# Adafruit_VEML7700_STEMMA_QT.net
KiCad netlist of a schematic drawn in Altium Designer
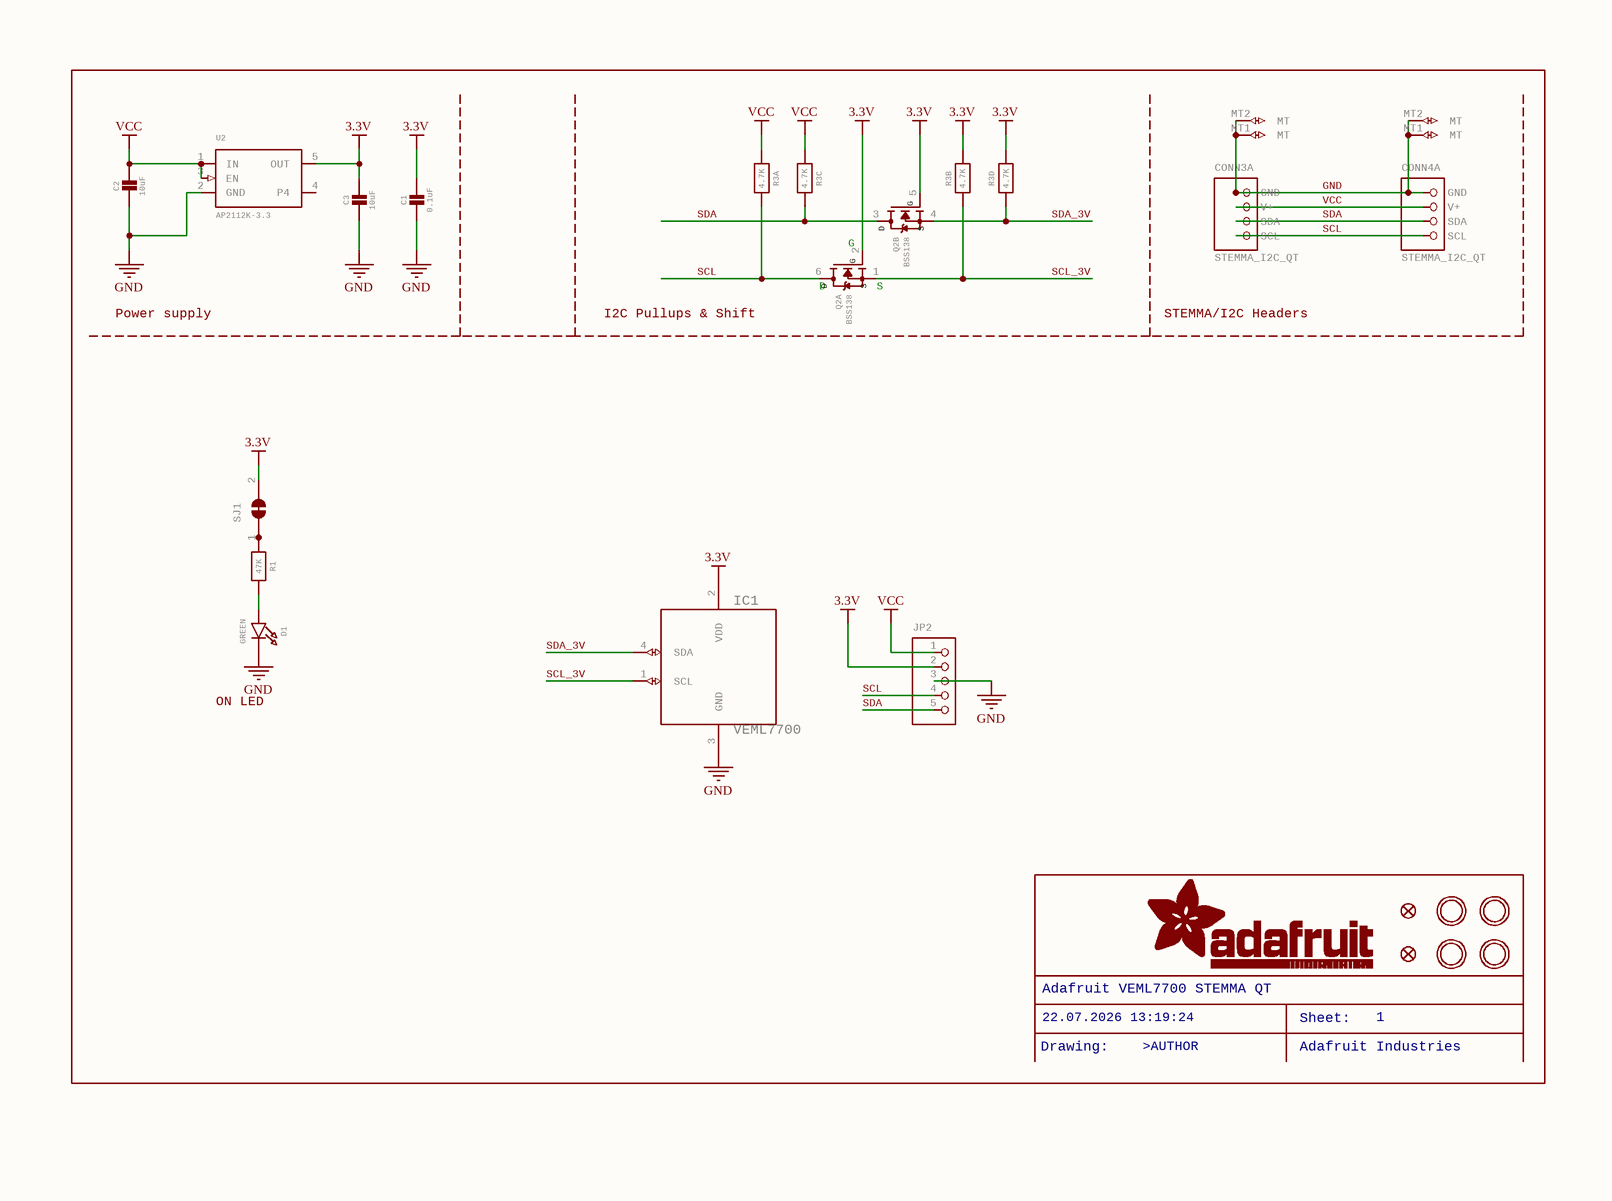
[diagram p0: Adafruit VEML7700 STEMMA QT.SchDoc]

(export (version "E")
  (design (tool "Eeschema 10.0.6"))
  (components
    (comp (ref "C1")
      (value "0.1uF")
      (footprint "0603-NO")
      (libsource (lib "microbuilder") (part "CAP_CERAMIC0603_NO"))
    )
    (comp (ref "C2")
      (value "10uF")
      (footprint "0805-NO")
      (libsource (lib "microbuilder") (part "CAP_CERAMIC0805-NOOUTLINE"))
    )
    (comp (ref "C3")
      (value "10uF")
      (footprint "0805-NO")
      (libsource (lib "microbuilder") (part "CAP_CERAMIC0805-NOOUTLINE"))
    )
    (comp (ref "CONN3")
      (value "STEMMA_I2C_QT")
      (footprint "JST_SH4")
      (libsource (lib "microbuilder") (part "STEMMA_I2C_QT"))
    )
    (comp (ref "CONN4")
      (value "STEMMA_I2C_QT")
      (footprint "JST_SH4")
      (libsource (lib "microbuilder") (part "STEMMA_I2C_QT"))
    )
    (comp (ref "D1")
      (value "GREEN")
      (footprint "CHIPLED_0603_NOOUTLINE")
      (libsource (lib "microbuilder") (part "LED0603_NOOUTLINE"))
    )
    (comp (ref "FID3")
      (value "FIDUCIAL_1MM")
      (footprint "FIDUCIAL_1MM")
      (description "Fiducial Alignment Points   Various fiducial points for machine vision alignment.")
      (libsource (lib "microbuilder") (part "FIDUCIAL_1MM"))
    )
    (comp (ref "FID4")
      (value "FIDUCIAL_1MM")
      (footprint "FIDUCIAL_1MM")
      (description "Fiducial Alignment Points   Various fiducial points for machine vision alignment.")
      (libsource (lib "microbuilder") (part "FIDUCIAL_1MM"))
    )
    (comp (ref "IC1")
      (value "VEML7700")
      (footprint "VEML7700")
      (fields (field (name "VEML7700") "VEML7700"))
      (libsource (lib "VEML7700") (part "VEML7700"))
    )
    (comp (ref "JP2")
      (value "HEADER-1X5ROUND")
      (footprint "1X05_ROUND")
      (description "PIN HEADER")
      (libsource (lib "microbuilder") (part "HEADER-1X5ROUND"))
    )
    (comp (ref "Q2")
      (value "BSS138")
      (footprint "SOT363")
      (description "Dual N-Channel MOSFET   SOT363 (2.0x1.25mm) 2N7002PS - 60V, 320mA [Digikey: 568-5984-1-ND]")
      (fields (field (name "D") "D") (field (name "S") "S") (field (name "G") "G"))
      (libsource (lib "microbuilder") (part "MOSFET-N_DUAL"))
    )
    (comp (ref "R1")
      (value "47K")
      (footprint "0603-NO")
      (libsource (lib "microbuilder") (part "RESISTOR_0603_NOOUT"))
    )
    (comp (ref "R3")
      (value "4.7K")
      (footprint "RESPACK_4X0603")
      (description "Resistor Packs (4 resistors)   4 x 0603 10K 1/16W - Digikey: YC164J-10KCT-ND")
      (libsource (lib "microbuilder") (part "RESISTOR_4PACK"))
    )
    (comp (ref "SJ1")
      (value "SOLDERJUMPER_CLOSED")
      (footprint "SOLDERJUMPER_CLOSEDWIRE")
      (libsource (lib "microbuilder") (part "SOLDERJUMPER_CLOSED"))
    )
    (comp (ref "U$1")
      (value "MOUNTINGHOLE2.5")
      (footprint "MOUNTINGHOLE_2.5_PLATED")
      (description "Mounting Hole   For #2 screws (0.086\"/2.18mm width, 0.094\"/2.4mm hole) use 2.5mm")
      (fields (field (name "LIBRARYNAME") "adafruit_electromech"))
      (libsource (lib "adafruit_electromech") (part "MOUNTINGHOLE2.5"))
    )
    (comp (ref "U$17")
      (value "MOUNTINGHOLE2.5")
      (footprint "MOUNTINGHOLE_2.5_PLATED")
      (description "Mounting Hole   For #2 screws (0.086\"/2.18mm width, 0.094\"/2.4mm hole) use 2.5mm")
      (fields (field (name "LIBRARYNAME") "adafruit_electromech"))
      (libsource (lib "adafruit_electromech") (part "MOUNTINGHOLE2.5"))
    )
    (comp (ref "U$19")
      (value "MOUNTINGHOLE2.5")
      (footprint "MOUNTINGHOLE_2.5_PLATED")
      (description "Mounting Hole   For #2 screws (0.086\"/2.18mm width, 0.094\"/2.4mm hole) use 2.5mm")
      (fields (field (name "LIBRARYNAME") "adafruit_electromech"))
      (libsource (lib "adafruit_electromech") (part "MOUNTINGHOLE2.5"))
    )
    (comp (ref "U$21")
      (value "MOUNTINGHOLE2.5")
      (footprint "MOUNTINGHOLE_2.5_PLATED")
      (description "Mounting Hole   For #2 screws (0.086\"/2.18mm width, 0.094\"/2.4mm hole) use 2.5mm")
      (fields (field (name "LIBRARYNAME") "adafruit_electromech"))
      (libsource (lib "adafruit_electromech") (part "MOUNTINGHOLE2.5"))
    )
    (comp (ref "U2")
      (value "AP2112K-3.3")
      (footprint "SOT23-5")
      (libsource (lib "adafruit_power") (part "VREG_SOT23-5"))
    )
  )
  (nets
    (net (code "1") (name "/SCL") (class "Default")
      (node (ref "CONN3") (pin "4") (pinfunction "SCL_4") (pintype "passive"))
      (node (ref "CONN4") (pin "4") (pinfunction "SCL_4") (pintype "passive"))
      (node (ref "JP2") (pin "4") (pinfunction "4_4") (pintype "passive"))
      (node (ref "Q2") (pin "6") (pinfunction "D_6") (pintype "bidirectional"))
      (node (ref "R3") (pin "8") (pinfunction "2_8") (pintype "passive"))
    )
    (net (code "2") (name "/SCL_3V") (class "Default")
      (node (ref "IC1") (pin "1") (pinfunction "SCL_1") (pintype "bidirectional"))
      (node (ref "Q2") (pin "1") (pinfunction "S_1") (pintype "bidirectional"))
      (node (ref "R3") (pin "7") (pinfunction "2_7") (pintype "passive"))
    )
    (net (code "3") (name "/SDA") (class "Default")
      (node (ref "CONN3") (pin "3") (pinfunction "SDA_3") (pintype "passive"))
      (node (ref "CONN4") (pin "3") (pinfunction "SDA_3") (pintype "passive"))
      (node (ref "JP2") (pin "5") (pinfunction "5_5") (pintype "passive"))
      (node (ref "Q2") (pin "3") (pinfunction "D_3") (pintype "bidirectional"))
      (node (ref "R3") (pin "6") (pinfunction "2_6") (pintype "passive"))
    )
    (net (code "4") (name "/SDA_3V") (class "Default")
      (node (ref "IC1") (pin "4") (pinfunction "SDA_4") (pintype "bidirectional"))
      (node (ref "Q2") (pin "4") (pinfunction "S_4") (pintype "bidirectional"))
      (node (ref "R3") (pin "5") (pinfunction "2_5") (pintype "passive"))
    )
    (net (code "5") (name "3.3V") (class "Default")
      (node (ref "C1") (pin "1") (pinfunction "1_1") (pintype "passive"))
      (node (ref "C3") (pin "1") (pinfunction "1_1") (pintype "passive"))
      (node (ref "IC1") (pin "2") (pinfunction "VDD_2") (pintype "power_in"))
      (node (ref "JP2") (pin "2") (pinfunction "2_2") (pintype "passive"))
      (node (ref "Q2") (pin "2") (pinfunction "G_2") (pintype "bidirectional"))
      (node (ref "Q2") (pin "5") (pinfunction "G_5") (pintype "bidirectional"))
      (node (ref "R3") (pin "2") (pinfunction "1_2") (pintype "passive"))
      (node (ref "R3") (pin "4") (pinfunction "1_4") (pintype "passive"))
      (node (ref "SJ1") (pin "2") (pinfunction "2_2") (pintype "passive"))
      (node (ref "U2") (pin "5") (pinfunction "OUT_5") (pintype "power_in"))
    )
    (net (code "6") (name "GND") (class "Default")
      (node (ref "C1") (pin "2") (pinfunction "2_2") (pintype "passive"))
      (node (ref "C2") (pin "2") (pinfunction "2_2") (pintype "passive"))
      (node (ref "C3") (pin "2") (pinfunction "2_2") (pintype "passive"))
      (node (ref "CONN3") (pin "1") (pinfunction "GND_1") (pintype "passive"))
      (node (ref "CONN3") (pin "MT1") (pinfunction "MT_MT1") (pintype "bidirectional"))
      (node (ref "CONN3") (pin "MT2") (pinfunction "MT_MT2") (pintype "bidirectional"))
      (node (ref "CONN4") (pin "1") (pinfunction "GND_1") (pintype "passive"))
      (node (ref "CONN4") (pin "MT1") (pinfunction "MT_MT1") (pintype "bidirectional"))
      (node (ref "CONN4") (pin "MT2") (pinfunction "MT_MT2") (pintype "bidirectional"))
      (node (ref "D1") (pin "C") (pinfunction "C_C") (pintype "passive"))
      (node (ref "IC1") (pin "3") (pinfunction "GND_3") (pintype "power_in"))
      (node (ref "JP2") (pin "3") (pinfunction "3_3") (pintype "passive"))
      (node (ref "U2") (pin "2") (pinfunction "GND_2") (pintype "power_in"))
    )
    (net (code "7") (name "Net-(D1-PadA)") (class "Default")
      (node (ref "D1") (pin "A") (pinfunction "A_A") (pintype "passive"))
      (node (ref "R1") (pin "2") (pinfunction "2_2") (pintype "passive"))
    )
    (net (code "8") (name "Net-(R1-Pad1)") (class "Default")
      (node (ref "R1") (pin "1") (pinfunction "1_1") (pintype "passive"))
      (node (ref "SJ1") (pin "1") (pinfunction "1_1") (pintype "passive"))
    )
    (net (code "9") (name "VCC") (class "Default")
      (node (ref "C2") (pin "1") (pinfunction "1_1") (pintype "passive"))
      (node (ref "CONN3") (pin "2") (pinfunction "V+_2") (pintype "passive"))
      (node (ref "CONN4") (pin "2") (pinfunction "V+_2") (pintype "passive"))
      (node (ref "JP2") (pin "1") (pinfunction "1_1") (pintype "passive"))
      (node (ref "R3") (pin "1") (pinfunction "1_1") (pintype "passive"))
      (node (ref "R3") (pin "3") (pinfunction "1_3") (pintype "passive"))
      (node (ref "U2") (pin "1") (pinfunction "IN_1") (pintype "power_in"))
      (node (ref "U2") (pin "3") (pinfunction "EN_3") (pintype "input"))
    )
    (net (code "10") (name "unconnected-(U2-P4-Pad4)") (class "Default")
      (node (ref "U2") (pin "4") (pinfunction "P4_4") (pintype "bidirectional"))
    )
  )
)
